# pcb_aux_motors.net
KiCad netlist of a schematic drawn in EAGLE
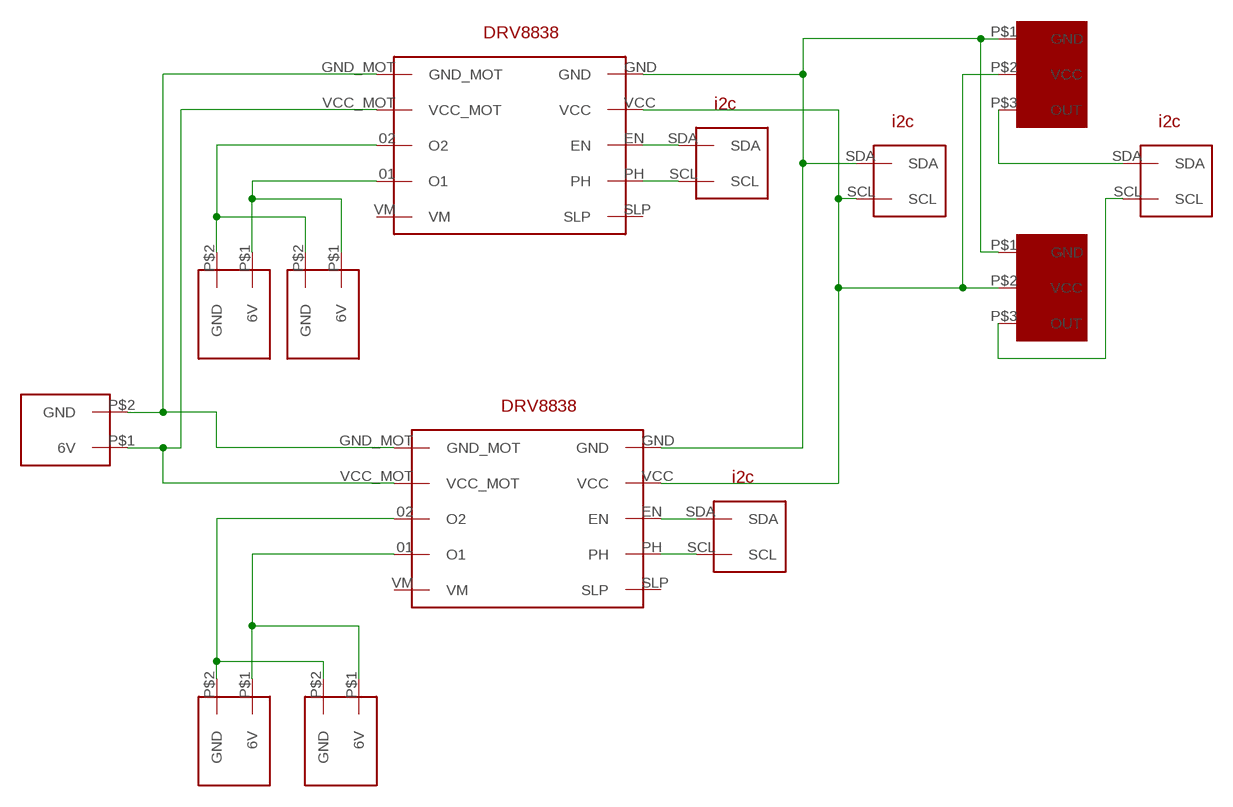
[diagram p0: schematic, sheet 1]

(export (version "E")
  (design (tool "Eeschema 10.0.6"))
  (components
    (comp (ref "EN/PH1")
      (value "I2C")
      (footprint "eagle-import:I2C")
      (libsource (lib "eagle-import") (part "I2C"))
    )
    (comp (ref "EN/PH2")
      (value "I2C")
      (footprint "eagle-import:I2C")
      (libsource (lib "eagle-import") (part "I2C"))
    )
    (comp (ref "ENCODERS")
      (value "I2C")
      (footprint "eagle-import:I2C")
      (libsource (lib "eagle-import") (part "I2C"))
    )
    (comp (ref "U$1")
      (value "MOTOR")
      (footprint "eagle-import:MOTOR")
      (libsource (lib "eagle-import") (part "MOTOR"))
    )
    (comp (ref "U$2")
      (value "ENCODER")
      (footprint "eagle-import:ENCODER")
      (libsource (lib "eagle-import") (part "ENCODER"))
    )
    (comp (ref "U$3")
      (value "ENCODER")
      (footprint "eagle-import:ENCODER")
      (libsource (lib "eagle-import") (part "ENCODER"))
    )
    (comp (ref "U$4")
      (value "DRV8838")
      (footprint "eagle-import:DRV8838")
      (libsource (lib "eagle-import") (part "DRV8838"))
    )
    (comp (ref "U$8")
      (value "MOTOR")
      (footprint "eagle-import:MOTOR")
      (libsource (lib "eagle-import") (part "MOTOR"))
    )
    (comp (ref "U$9")
      (value "MOTOR")
      (footprint "eagle-import:MOTOR")
      (libsource (lib "eagle-import") (part "MOTOR"))
    )
    (comp (ref "U$10")
      (value "MOTOR")
      (footprint "eagle-import:MOTOR")
      (libsource (lib "eagle-import") (part "MOTOR"))
    )
    (comp (ref "U$11")
      (value "MOTOR")
      (footprint "eagle-import:MOTOR")
      (libsource (lib "eagle-import") (part "MOTOR"))
    )
    (comp (ref "U$12")
      (value "DRV8838")
      (footprint "eagle-import:DRV8838")
      (libsource (lib "eagle-import") (part "DRV8838"))
    )
    (comp (ref "VCC/GND")
      (value "I2C")
      (footprint "eagle-import:I2C")
      (libsource (lib "eagle-import") (part "I2C"))
    )
  )
  (nets
    (net (code "1") (name "Net-(EN/PH1-PadSCL)") (class "Default")
      (node (ref "EN/PH1") (pin "SCL") (pinfunction "SCL_SCL") (pintype "bidirectional"))
      (node (ref "U$4") (pin "PH") (pinfunction "PH_PH") (pintype "bidirectional"))
    )
    (net (code "2") (name "Net-(EN/PH1-PadSDA)") (class "Default")
      (node (ref "EN/PH1") (pin "SDA") (pinfunction "SDA_SDA") (pintype "bidirectional"))
      (node (ref "U$4") (pin "EN") (pinfunction "EN_EN") (pintype "bidirectional"))
    )
    (net (code "3") (name "Net-(EN/PH2-PadSCL)") (class "Default")
      (node (ref "EN/PH2") (pin "SCL") (pinfunction "SCL_SCL") (pintype "bidirectional"))
      (node (ref "U$12") (pin "PH") (pinfunction "PH_PH") (pintype "bidirectional"))
    )
    (net (code "4") (name "Net-(EN/PH2-PadSDA)") (class "Default")
      (node (ref "EN/PH2") (pin "SDA") (pinfunction "SDA_SDA") (pintype "bidirectional"))
      (node (ref "U$12") (pin "EN") (pinfunction "EN_EN") (pintype "bidirectional"))
    )
    (net (code "5") (name "Net-(U$1-6V)") (class "Default")
      (node (ref "U$1") (pin "P$1") (pinfunction "6V_P$1") (pintype "bidirectional"))
      (node (ref "U$4") (pin "01") (pinfunction "O1_01") (pintype "bidirectional"))
      (node (ref "U$8") (pin "P$1") (pinfunction "6V_P$1") (pintype "bidirectional"))
    )
    (net (code "6") (name "Net-(U$1-GND)") (class "Default")
      (node (ref "U$1") (pin "P$2") (pinfunction "GND_P$2") (pintype "bidirectional"))
      (node (ref "U$4") (pin "02") (pinfunction "O2_02") (pintype "bidirectional"))
      (node (ref "U$8") (pin "P$2") (pinfunction "GND_P$2") (pintype "bidirectional"))
    )
    (net (code "7") (name "Net-(U$2-GND)") (class "Default")
      (node (ref "U$12") (pin "GND") (pinfunction "GND_GND") (pintype "bidirectional"))
      (node (ref "U$2") (pin "P$1") (pinfunction "GND_P$1") (pintype "bidirectional"))
      (node (ref "U$3") (pin "P$1") (pinfunction "GND_P$1") (pintype "bidirectional"))
      (node (ref "U$4") (pin "GND") (pinfunction "GND_GND") (pintype "bidirectional"))
      (node (ref "VCC/GND") (pin "SDA") (pinfunction "SDA_SDA") (pintype "bidirectional"))
    )
    (net (code "8") (name "Net-(U$2-OUT)") (class "Default")
      (node (ref "ENCODERS") (pin "SDA") (pinfunction "SDA_SDA") (pintype "bidirectional"))
      (node (ref "U$2") (pin "P$3") (pinfunction "OUT_P$3") (pintype "bidirectional"))
    )
    (net (code "9") (name "Net-(U$2-VCC)") (class "Default")
      (node (ref "U$12") (pin "VCC") (pinfunction "VCC_VCC") (pintype "bidirectional"))
      (node (ref "U$2") (pin "P$2") (pinfunction "VCC_P$2") (pintype "bidirectional"))
      (node (ref "U$3") (pin "P$2") (pinfunction "VCC_P$2") (pintype "bidirectional"))
      (node (ref "U$4") (pin "VCC") (pinfunction "VCC_VCC") (pintype "bidirectional"))
      (node (ref "VCC/GND") (pin "SCL") (pinfunction "SCL_SCL") (pintype "bidirectional"))
    )
    (net (code "10") (name "Net-(U$3-OUT)") (class "Default")
      (node (ref "ENCODERS") (pin "SCL") (pinfunction "SCL_SCL") (pintype "bidirectional"))
      (node (ref "U$3") (pin "P$3") (pinfunction "OUT_P$3") (pintype "bidirectional"))
    )
    (net (code "11") (name "Net-(U$10-6V)") (class "Default")
      (node (ref "U$10") (pin "P$1") (pinfunction "6V_P$1") (pintype "bidirectional"))
      (node (ref "U$12") (pin "01") (pinfunction "O1_01") (pintype "bidirectional"))
      (node (ref "U$9") (pin "P$1") (pinfunction "6V_P$1") (pintype "bidirectional"))
    )
    (net (code "12") (name "Net-(U$10-GND)") (class "Default")
      (node (ref "U$10") (pin "P$2") (pinfunction "GND_P$2") (pintype "bidirectional"))
      (node (ref "U$12") (pin "02") (pinfunction "O2_02") (pintype "bidirectional"))
      (node (ref "U$9") (pin "P$2") (pinfunction "GND_P$2") (pintype "bidirectional"))
    )
    (net (code "13") (name "Net-(U$11-6V)") (class "Default")
      (node (ref "U$11") (pin "P$1") (pinfunction "6V_P$1") (pintype "bidirectional"))
      (node (ref "U$12") (pin "VCC_MOT") (pinfunction "VCC_MOT_VCC_MOT") (pintype "bidirectional"))
      (node (ref "U$4") (pin "VCC_MOT") (pinfunction "VCC_MOT_VCC_MOT") (pintype "bidirectional"))
    )
    (net (code "14") (name "Net-(U$11-GND)") (class "Default")
      (node (ref "U$11") (pin "P$2") (pinfunction "GND_P$2") (pintype "bidirectional"))
      (node (ref "U$12") (pin "GND_MOT") (pinfunction "GND_MOT_GND_MOT") (pintype "bidirectional"))
      (node (ref "U$4") (pin "GND_MOT") (pinfunction "GND_MOT_GND_MOT") (pintype "bidirectional"))
    )
    (net (code "15") (name "unconnected-(U$4-PadSLP)") (class "Default")
      (node (ref "U$4") (pin "SLP") (pinfunction "SLP_SLP") (pintype "bidirectional"))
    )
    (net (code "16") (name "unconnected-(U$4-PadVM)") (class "Default")
      (node (ref "U$4") (pin "VM") (pinfunction "VM_VM") (pintype "bidirectional"))
    )
    (net (code "17") (name "unconnected-(U$12-PadSLP)") (class "Default")
      (node (ref "U$12") (pin "SLP") (pinfunction "SLP_SLP") (pintype "bidirectional"))
    )
    (net (code "18") (name "unconnected-(U$12-PadVM)") (class "Default")
      (node (ref "U$12") (pin "VM") (pinfunction "VM_VM") (pintype "bidirectional"))
    )
  )
)
